# MCU.net
KiCad netlist of a schematic drawn in Altium Designer
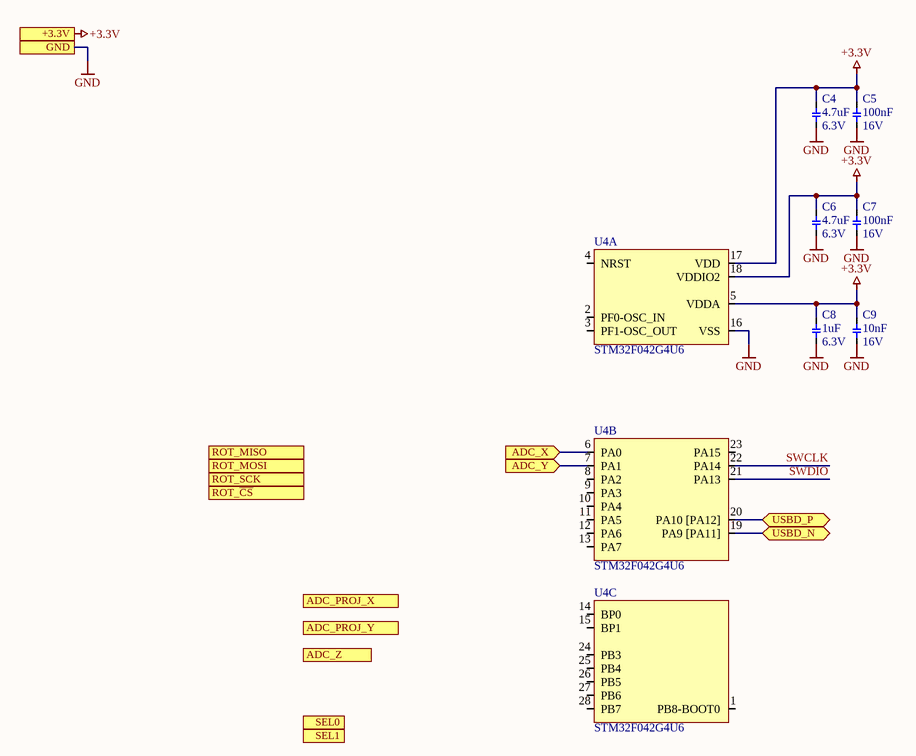
[diagram p0: MCU.SchDoc]

(export (version "E")
  (design (tool "Eeschema 10.0.6"))
  (components
    (comp (ref "C4")
      (value "4.7uF")
      (footprint "CX7R0603K")
      (description "SMD Capacitor")
      (fields (field (name "VALUE2") "6.3V") (field (name "Comment") "06036C475JAT2A"))
      (libsource (lib "ChaoticCircuits") (part "kyocera-C-X7R-0603"))
    )
    (comp (ref "C5")
      (value "100nF")
      (footprint "CX7R0402C")
      (description "SMD Capacitor")
      (fields (field (name "VALUE2") "16V") (field (name "Comment") "0402YC104JAT2A"))
      (libsource (lib "ChaoticCircuits") (part "kyocera-C-X7R-0402"))
    )
    (comp (ref "C6")
      (value "4.7uF")
      (footprint "CX7R0603K")
      (description "SMD Capacitor")
      (fields (field (name "VALUE2") "6.3V") (field (name "Comment") "06036C475JAT2A"))
      (libsource (lib "ChaoticCircuits") (part "kyocera-C-X7R-0603"))
    )
    (comp (ref "C7")
      (value "100nF")
      (footprint "CX7R0402C")
      (description "SMD Capacitor")
      (fields (field (name "VALUE2") "16V") (field (name "Comment") "0402YC104JAT2A"))
      (libsource (lib "ChaoticCircuits") (part "kyocera-C-X7R-0402"))
    )
    (comp (ref "C8")
      (value "1uF")
      (footprint "CX7R0603K")
      (description "SMD Capacitor")
      (fields (field (name "VALUE2") "6.3V") (field (name "Comment") "06036C105JAT2A"))
      (libsource (lib "ChaoticCircuits") (part "kyocera-C-X7R-0603"))
    )
    (comp (ref "C9")
      (value "10nF")
      (footprint "CX7R0402C")
      (description "SMD Capacitor")
      (fields (field (name "VALUE2") "16V") (field (name "Comment") "0402YC103JAT2A"))
      (libsource (lib "ChaoticCircuits") (part "kyocera-C-X7R-0402"))
    )
    (comp (ref "U4")
      (value "STM32F042G4U6")
      (footprint "UFQFPN28_0.5_C")
      (description "ARM® Cortex®-M0 series Microcontroller IC 32-Bit 48MHz 16KB (16K x 8) FLASH 28-UFQFPN (4x4)")
      (libsource (lib "ChaoticCircuits") (part "STM32F042G4U6"))
    )
  )
  (nets
    (net (code "1") (name "+3.3V") (class "Default")
      (node (ref "C4") (pin "2") (pinfunction "2_2") (pintype "passive"))
      (node (ref "C5") (pin "2") (pinfunction "2_2") (pintype "passive"))
      (node (ref "C6") (pin "2") (pinfunction "2_2") (pintype "passive"))
      (node (ref "C7") (pin "2") (pinfunction "2_2") (pintype "passive"))
      (node (ref "C8") (pin "2") (pinfunction "2_2") (pintype "passive"))
      (node (ref "C9") (pin "2") (pinfunction "2_2") (pintype "passive"))
      (node (ref "U4") (pin "17") (pinfunction "VDD_17") (pintype "passive"))
      (node (ref "U4") (pin "18") (pinfunction "VDDIO2_18") (pintype "passive"))
      (node (ref "U4") (pin "5") (pinfunction "VDDA_5") (pintype "passive"))
    )
    (net (code "4") (name "/ADC_X") (class "Default")
      (node (ref "U4") (pin "6") (pinfunction "PA0_6") (pintype "passive"))
    )
    (net (code "5") (name "/ADC_Y") (class "Default")
      (node (ref "U4") (pin "7") (pinfunction "PA1_7") (pintype "passive"))
    )
    (net (code "13") (name "/SWCLK") (class "Default")
      (node (ref "U4") (pin "22") (pinfunction "PA14_22") (pintype "passive"))
    )
    (net (code "14") (name "/SWDIO") (class "Default")
      (node (ref "U4") (pin "21") (pinfunction "PA13_21") (pintype "passive"))
    )
    (net (code "15") (name "/USBD_N") (class "Default")
      (node (ref "U4") (pin "19") (pinfunction "PA9_[PA11]_19") (pintype "passive"))
    )
    (net (code "16") (name "/USBD_P") (class "Default")
      (node (ref "U4") (pin "20") (pinfunction "PA10_[PA12]_20") (pintype "passive"))
    )
    (net (code "17") (name "GND") (class "Default")
      (node (ref "C4") (pin "1") (pinfunction "1_1") (pintype "passive"))
      (node (ref "C5") (pin "1") (pinfunction "1_1") (pintype "passive"))
      (node (ref "C6") (pin "1") (pinfunction "1_1") (pintype "passive"))
      (node (ref "C7") (pin "1") (pinfunction "1_1") (pintype "passive"))
      (node (ref "C8") (pin "1") (pinfunction "1_1") (pintype "passive"))
      (node (ref "C9") (pin "1") (pinfunction "1_1") (pintype "passive"))
      (node (ref "U4") (pin "16") (pinfunction "VSS_16") (pintype "passive"))
    )
    (net (code "18") (name "unconnected-(U4A-NRST-Pad4)") (class "Default")
      (node (ref "U4") (pin "4") (pinfunction "NRST_4") (pintype "passive"))
    )
    (net (code "19") (name "unconnected-(U4A-PF0-OSC_IN-Pad2)") (class "Default")
      (node (ref "U4") (pin "2") (pinfunction "PF0-OSC_IN_2") (pintype "passive"))
    )
    (net (code "20") (name "unconnected-(U4A-PF1-OSC_OUT-Pad3)") (class "Default")
      (node (ref "U4") (pin "3") (pinfunction "PF1-OSC_OUT_3") (pintype "passive"))
    )
    (net (code "21") (name "unconnected-(U4B-PA2-Pad8)") (class "Default")
      (node (ref "U4") (pin "8") (pinfunction "PA2_8") (pintype "passive"))
    )
    (net (code "22") (name "unconnected-(U4B-PA3-Pad9)") (class "Default")
      (node (ref "U4") (pin "9") (pinfunction "PA3_9") (pintype "passive"))
    )
    (net (code "23") (name "unconnected-(U4B-PA4-Pad10)") (class "Default")
      (node (ref "U4") (pin "10") (pinfunction "PA4_10") (pintype "passive"))
    )
    (net (code "24") (name "unconnected-(U4B-PA5-Pad11)") (class "Default")
      (node (ref "U4") (pin "11") (pinfunction "PA5_11") (pintype "passive"))
    )
    (net (code "25") (name "unconnected-(U4B-PA6-Pad12)") (class "Default")
      (node (ref "U4") (pin "12") (pinfunction "PA6_12") (pintype "passive"))
    )
    (net (code "26") (name "unconnected-(U4B-PA7-Pad13)") (class "Default")
      (node (ref "U4") (pin "13") (pinfunction "PA7_13") (pintype "passive"))
    )
    (net (code "27") (name "unconnected-(U4B-PA15-Pad23)") (class "Default")
      (node (ref "U4") (pin "23") (pinfunction "PA15_23") (pintype "passive"))
    )
    (net (code "28") (name "unconnected-(U4C-BP0-Pad14)") (class "Default")
      (node (ref "U4") (pin "14") (pinfunction "BP0_14") (pintype "passive"))
    )
    (net (code "29") (name "unconnected-(U4C-BP1-Pad15)") (class "Default")
      (node (ref "U4") (pin "15") (pinfunction "BP1_15") (pintype "passive"))
    )
    (net (code "30") (name "unconnected-(U4C-PB3-Pad24)") (class "Default")
      (node (ref "U4") (pin "24") (pinfunction "PB3_24") (pintype "passive"))
    )
    (net (code "31") (name "unconnected-(U4C-PB4-Pad25)") (class "Default")
      (node (ref "U4") (pin "25") (pinfunction "PB4_25") (pintype "passive"))
    )
    (net (code "32") (name "unconnected-(U4C-PB5-Pad26)") (class "Default")
      (node (ref "U4") (pin "26") (pinfunction "PB5_26") (pintype "passive"))
    )
    (net (code "33") (name "unconnected-(U4C-PB6-Pad27)") (class "Default")
      (node (ref "U4") (pin "27") (pinfunction "PB6_27") (pintype "passive"))
    )
    (net (code "34") (name "unconnected-(U4C-PB7-Pad28)") (class "Default")
      (node (ref "U4") (pin "28") (pinfunction "PB7_28") (pintype "passive"))
    )
    (net (code "35") (name "unconnected-(U4C-PB8-BOOT0-Pad1)") (class "Default")
      (node (ref "U4") (pin "1") (pinfunction "PB8-BOOT0_1") (pintype "passive"))
    )
  )
)
